# SensorBoard-v13.net
KiCad netlist of a schematic drawn in EAGLE
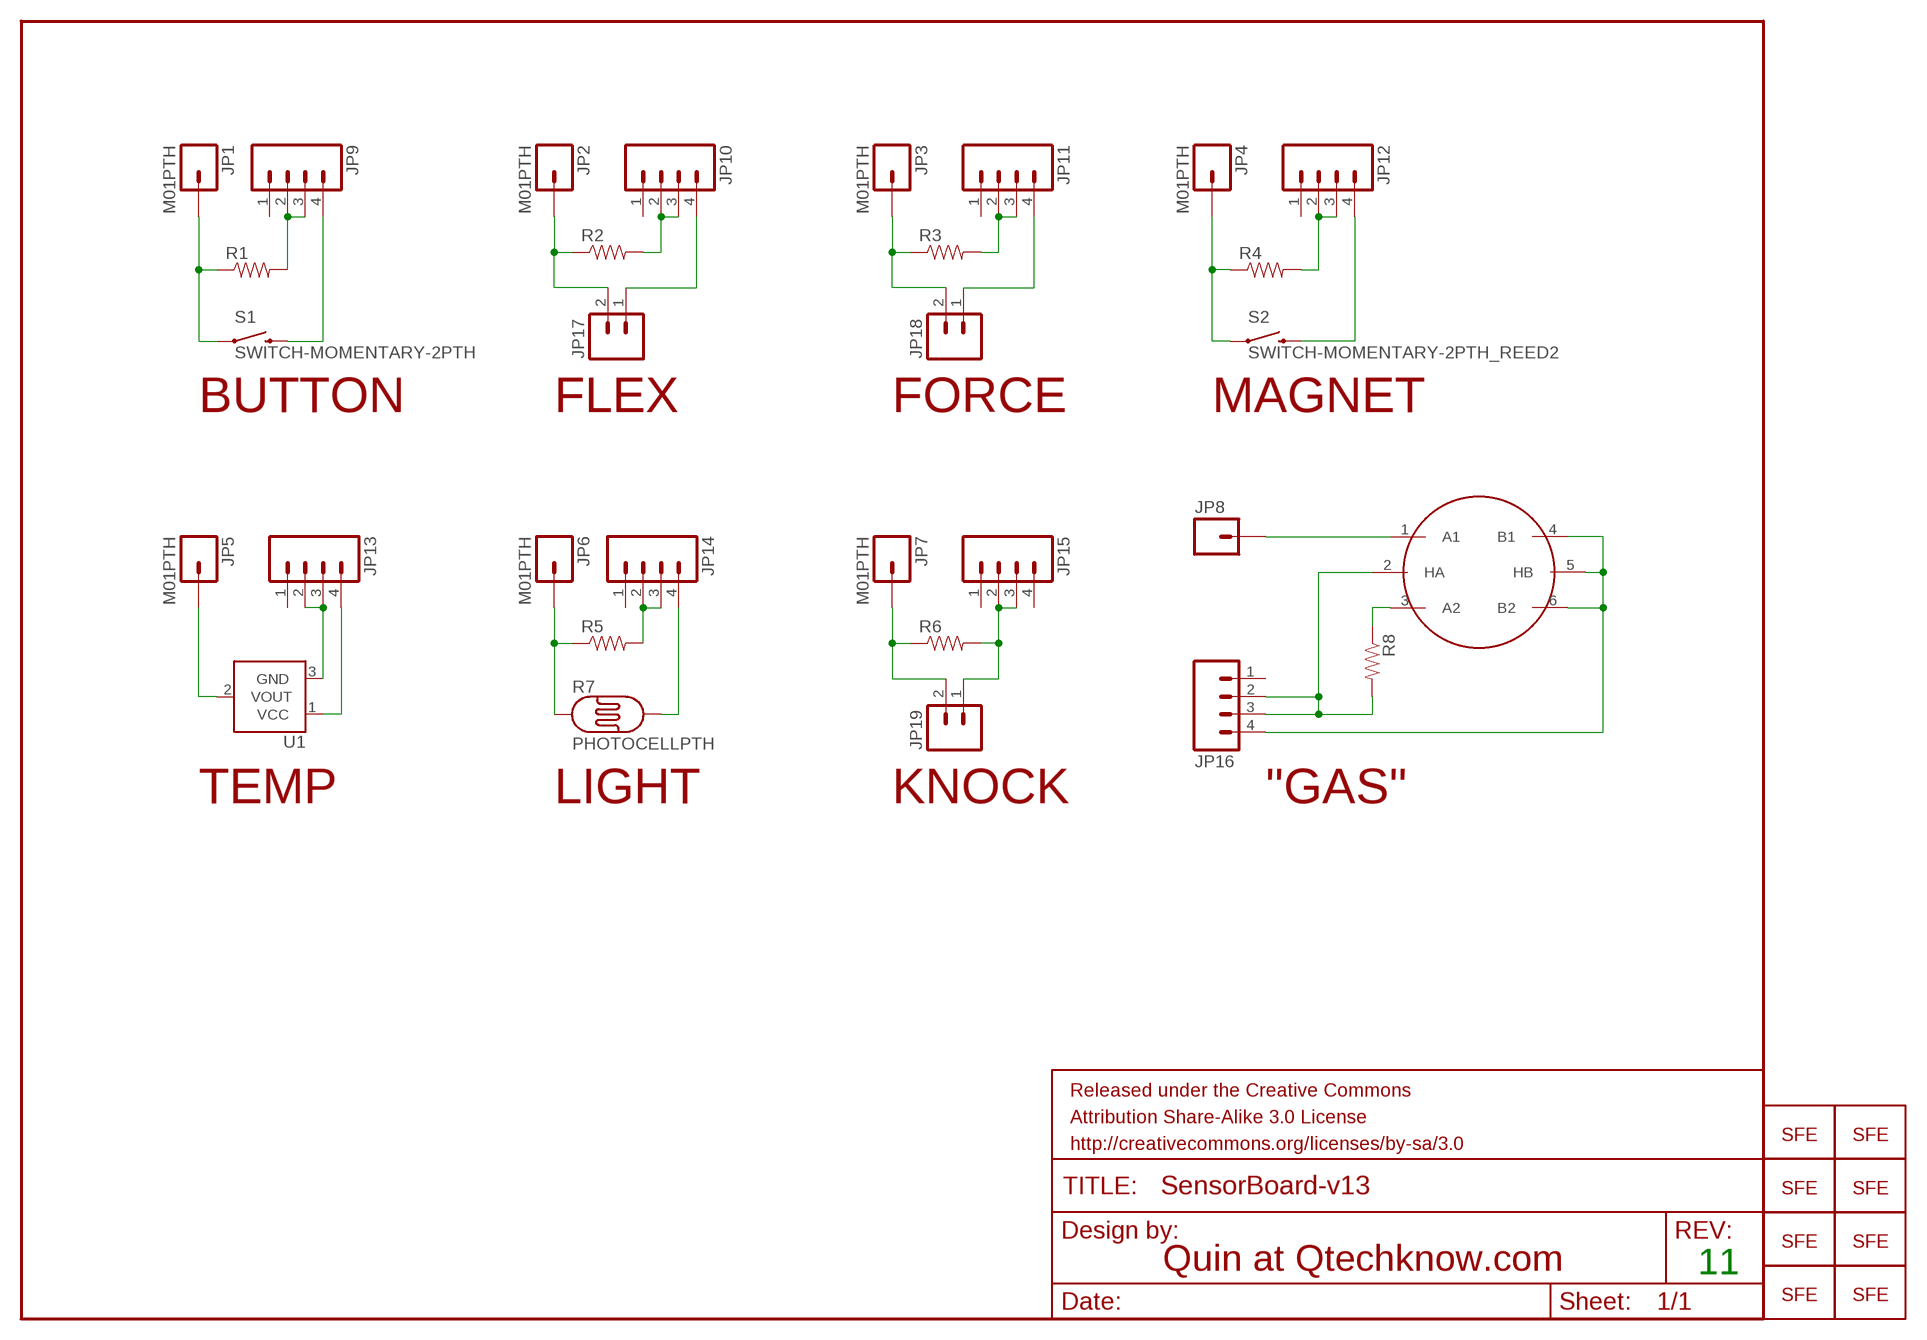
[diagram p0: schematic, sheet 1]

(export (version "E")
  (design (tool "Eeschema 10.0.6"))
  (components
    (comp (ref "FRAME1")
      (value "FRAME-LETTER")
      (footprint "eagle-import:CREATIVE_COMMONS")
      (libsource (lib "eagle-import") (part "FRAME-LETTER"))
    )
    (comp (ref "JP1")
      (value "M01PTH")
      (footprint "eagle-import:1X01")
      (libsource (lib "eagle-import") (part "2_1_SFE Connectors_M01PTH"))
    )
    (comp (ref "JP2")
      (value "M01PTH")
      (footprint "eagle-import:1X01")
      (libsource (lib "eagle-import") (part "2_2_SFE Connectors_M01PTH"))
    )
    (comp (ref "JP3")
      (value "M01PTH")
      (footprint "eagle-import:1X01")
      (libsource (lib "eagle-import") (part "2_3_SFE Connectors_M01PTH"))
    )
    (comp (ref "JP4")
      (value "M01PTH")
      (footprint "eagle-import:1X01")
      (libsource (lib "eagle-import") (part "2_6_SFE Connectors_M01PTH"))
    )
    (comp (ref "JP5")
      (value "M01PTH")
      (footprint "eagle-import:1X01")
      (libsource (lib "eagle-import") (part "2_7_SFE Connectors_M01PTH"))
    )
    (comp (ref "JP6")
      (value "M01PTH")
      (footprint "eagle-import:1X01")
      (libsource (lib "eagle-import") (part "2_5_SFE Connectors_M01PTH"))
    )
    (comp (ref "JP7")
      (value "M01PTH")
      (footprint "eagle-import:1X01")
      (libsource (lib "eagle-import") (part "2_4_SFE Connectors_M01PTH"))
    )
    (comp (ref "JP8")
      (value "M01PTH")
      (footprint "eagle-import:1X01")
      (libsource (lib "eagle-import") (part "M01PTH"))
    )
    (comp (ref "JP9")
      (value "M04PTH")
      (footprint "eagle-import:1X04")
      (libsource (lib "eagle-import") (part "2_1_SFE Connectors_M04PTH"))
    )
    (comp (ref "JP10")
      (value "M04PTH")
      (footprint "eagle-import:1X04")
      (libsource (lib "eagle-import") (part "2_2_SFE Connectors_M04PTH"))
    )
    (comp (ref "JP11")
      (value "M04PTH")
      (footprint "eagle-import:1X04")
      (libsource (lib "eagle-import") (part "2_3_SFE Connectors_M04PTH"))
    )
    (comp (ref "JP12")
      (value "M04PTH")
      (footprint "eagle-import:1X04")
      (libsource (lib "eagle-import") (part "2_6_SFE Connectors_M04PTH"))
    )
    (comp (ref "JP13")
      (value "M04PTH")
      (footprint "eagle-import:1X04")
      (libsource (lib "eagle-import") (part "2_7_SFE Connectors_M04PTH"))
    )
    (comp (ref "JP14")
      (value "M04PTH")
      (footprint "eagle-import:1X04")
      (libsource (lib "eagle-import") (part "2_5_SFE Connectors_M04PTH"))
    )
    (comp (ref "JP15")
      (value "M04PTH")
      (footprint "eagle-import:1X04")
      (libsource (lib "eagle-import") (part "2_4_SFE Connectors_M04PTH"))
    )
    (comp (ref "JP16")
      (value "M04PTH")
      (footprint "eagle-import:1X04")
      (libsource (lib "eagle-import") (part "M04PTH"))
    )
    (comp (ref "JP17")
      (value "M02PTH")
      (footprint "eagle-import:1X02")
      (libsource (lib "eagle-import") (part "M02PTH"))
    )
    (comp (ref "JP18")
      (value "M02PTH")
      (footprint "eagle-import:1X02")
      (libsource (lib "eagle-import") (part "2_3_SFE Connectors_M02PTH"))
    )
    (comp (ref "JP19")
      (value "M02PTH")
      (footprint "eagle-import:1X02")
      (libsource (lib "eagle-import") (part "2_4_SFE Connectors_M02PTH"))
    )
    (comp (ref "LOGO1")
      (value "LOGO-SFESK")
      (footprint "eagle-import:SFE-LOGO-FLAME")
      (libsource (lib "eagle-import") (part "LOGO-SFESK"))
    )
    (comp (ref "LOGO2")
      (value "LOGO-SFESK")
      (footprint "eagle-import:SFE-LOGO-FLAME")
      (libsource (lib "eagle-import") (part "LOGO-SFESK"))
    )
    (comp (ref "LOGO3")
      (value "LOGO-SFESK")
      (footprint "eagle-import:SFE-LOGO-FLAME")
      (libsource (lib "eagle-import") (part "LOGO-SFESK"))
    )
    (comp (ref "LOGO4")
      (value "LOGO-SFESK")
      (footprint "eagle-import:SFE-LOGO-FLAME")
      (libsource (lib "eagle-import") (part "LOGO-SFESK"))
    )
    (comp (ref "LOGO5")
      (value "LOGO-SFESK")
      (footprint "eagle-import:SFE-LOGO-FLAME")
      (libsource (lib "eagle-import") (part "LOGO-SFESK"))
    )
    (comp (ref "LOGO6")
      (value "LOGO-SFESK")
      (footprint "eagle-import:SFE-LOGO-FLAME")
      (libsource (lib "eagle-import") (part "LOGO-SFESK"))
    )
    (comp (ref "LOGO7")
      (value "LOGO-SFESK")
      (footprint "eagle-import:SFE-LOGO-FLAME")
      (libsource (lib "eagle-import") (part "LOGO-SFESK"))
    )
    (comp (ref "LOGO8")
      (value "LOGO-SFESK")
      (footprint "eagle-import:SFE-LOGO-FLAME")
      (libsource (lib "eagle-import") (part "LOGO-SFESK"))
    )
    (comp (ref "R1")
      (value "RESISTORAXIAL-0.3")
      (footprint "eagle-import:AXIAL-0.3")
      (libsource (lib "eagle-import") (part "2_1_SFE Passives_RESISTORAXIAL-0.3"))
    )
    (comp (ref "R2")
      (value "RESISTORAXIAL-0.3")
      (footprint "eagle-import:AXIAL-0.3")
      (libsource (lib "eagle-import") (part "2_2_SFE Passives_RESISTORAXIAL-0.3"))
    )
    (comp (ref "R3")
      (value "RESISTORAXIAL-0.3")
      (footprint "eagle-import:AXIAL-0.3")
      (libsource (lib "eagle-import") (part "2_3_SFE Passives_RESISTORAXIAL-0.3"))
    )
    (comp (ref "R4")
      (value "RESISTORAXIAL-0.3")
      (footprint "eagle-import:AXIAL-0.3")
      (libsource (lib "eagle-import") (part "2_6_SFE Passives_RESISTORAXIAL-0.3"))
    )
    (comp (ref "R5")
      (value "RESISTORAXIAL-0.3")
      (footprint "eagle-import:AXIAL-0.3")
      (libsource (lib "eagle-import") (part "2_5_SFE Passives_RESISTORAXIAL-0.3"))
    )
    (comp (ref "R6")
      (value "RESISTORAXIAL-0.3")
      (footprint "eagle-import:AXIAL-0.3")
      (libsource (lib "eagle-import") (part "2_4_SFE Passives_RESISTORAXIAL-0.3"))
    )
    (comp (ref "R7")
      (value "PHOTOCELLPTH")
      (footprint "eagle-import:PHOTOCELL")
      (libsource (lib "eagle-import") (part "PHOTOCELLPTH"))
    )
    (comp (ref "R8")
      (value "RESISTORAXIAL-0.3")
      (footprint "eagle-import:AXIAL-0.3")
      (libsource (lib "eagle-import") (part "RESISTORAXIAL-0.3"))
    )
    (comp (ref "S1")
      (value "SWITCH-MOMENTARY-2PTH")
      (footprint "eagle-import:TACTILE-PTH")
      (libsource (lib "eagle-import") (part "SWITCH-MOMENTARY-2PTH"))
    )
    (comp (ref "S2")
      (value "SWITCH-MOMENTARY-2PTH_REED2")
      (footprint "eagle-import:REED_SWITCH_PLASTIC")
      (libsource (lib "eagle-import") (part "2_6_SFE Electromechanical_SWITCH-MOMENTARY-2PTH_REED2"))
    )
    (comp (ref "U$1")
      (value "GAS-SENSORNEW")
      (footprint "eagle-import:GAS_SENSOR")
      (libsource (lib "eagle-import") (part "GAS-SENSORNEW"))
    )
    (comp (ref "U1")
      (value "TMP36GT9")
      (footprint "eagle-import:TO-92")
      (libsource (lib "eagle-import") (part "TMP36GT9"))
    )
  )
  (nets
    (net (code "1") (name "Net-(JP10-Pad4)") (class "Default")
      (node (ref "JP10") (pin "4") (pinfunction "4_4") (pintype "passive"))
      (node (ref "JP17") (pin "1") (pinfunction "1_1") (pintype "passive"))
    )
    (net (code "2") (name "Net-(JP11-Pad4)") (class "Default")
      (node (ref "JP11") (pin "4") (pinfunction "4_4") (pintype "passive"))
      (node (ref "JP18") (pin "1") (pinfunction "1_1") (pintype "passive"))
    )
    (net (code "3") (name "Net-(R1-1)") (class "Default")
      (node (ref "JP1") (pin "1") (pinfunction "1_1") (pintype "passive"))
      (node (ref "R1") (pin "P$1") (pinfunction "1_P$1") (pintype "passive"))
      (node (ref "S1") (pin "1") (pinfunction "1_1") (pintype "passive"))
    )
    (net (code "4") (name "Net-(R1-2)") (class "Default")
      (node (ref "JP9") (pin "2") (pinfunction "2_2") (pintype "passive"))
      (node (ref "JP9") (pin "3") (pinfunction "3_3") (pintype "passive"))
      (node (ref "R1") (pin "P$2") (pinfunction "2_P$2") (pintype "passive"))
    )
    (net (code "5") (name "Net-(R2-1)") (class "Default")
      (node (ref "JP17") (pin "2") (pinfunction "2_2") (pintype "passive"))
      (node (ref "JP2") (pin "1") (pinfunction "1_1") (pintype "passive"))
      (node (ref "R2") (pin "P$1") (pinfunction "1_P$1") (pintype "passive"))
    )
    (net (code "6") (name "Net-(R2-2)") (class "Default")
      (node (ref "JP10") (pin "2") (pinfunction "2_2") (pintype "passive"))
      (node (ref "JP10") (pin "3") (pinfunction "3_3") (pintype "passive"))
      (node (ref "R2") (pin "P$2") (pinfunction "2_P$2") (pintype "passive"))
    )
    (net (code "7") (name "Net-(R3-1)") (class "Default")
      (node (ref "JP18") (pin "2") (pinfunction "2_2") (pintype "passive"))
      (node (ref "JP3") (pin "1") (pinfunction "1_1") (pintype "passive"))
      (node (ref "R3") (pin "P$1") (pinfunction "1_P$1") (pintype "passive"))
    )
    (net (code "8") (name "Net-(R3-2)") (class "Default")
      (node (ref "JP11") (pin "2") (pinfunction "2_2") (pintype "passive"))
      (node (ref "JP11") (pin "3") (pinfunction "3_3") (pintype "passive"))
      (node (ref "R3") (pin "P$2") (pinfunction "2_P$2") (pintype "passive"))
    )
    (net (code "9") (name "Net-(R4-1)") (class "Default")
      (node (ref "JP4") (pin "1") (pinfunction "1_1") (pintype "passive"))
      (node (ref "R4") (pin "P$1") (pinfunction "1_P$1") (pintype "passive"))
      (node (ref "S2") (pin "P$1") (pinfunction "1_P$1") (pintype "passive"))
    )
    (net (code "10") (name "Net-(R4-2)") (class "Default")
      (node (ref "JP12") (pin "2") (pinfunction "2_2") (pintype "passive"))
      (node (ref "JP12") (pin "3") (pinfunction "3_3") (pintype "passive"))
      (node (ref "R4") (pin "P$2") (pinfunction "2_P$2") (pintype "passive"))
    )
    (net (code "11") (name "Net-(R5-1)") (class "Default")
      (node (ref "JP6") (pin "1") (pinfunction "1_1") (pintype "passive"))
      (node (ref "R5") (pin "P$1") (pinfunction "1_P$1") (pintype "passive"))
      (node (ref "R7") (pin "1") (pinfunction "P$1_1") (pintype "bidirectional"))
    )
    (net (code "12") (name "Net-(R5-2)") (class "Default")
      (node (ref "JP14") (pin "2") (pinfunction "2_2") (pintype "passive"))
      (node (ref "JP14") (pin "3") (pinfunction "3_3") (pintype "passive"))
      (node (ref "R5") (pin "P$2") (pinfunction "2_P$2") (pintype "passive"))
    )
    (net (code "13") (name "Net-(R6-1)") (class "Default")
      (node (ref "JP19") (pin "2") (pinfunction "2_2") (pintype "passive"))
      (node (ref "JP7") (pin "1") (pinfunction "1_1") (pintype "passive"))
      (node (ref "R6") (pin "P$1") (pinfunction "1_P$1") (pintype "passive"))
    )
    (net (code "14") (name "Net-(R6-2)") (class "Default")
      (node (ref "JP15") (pin "2") (pinfunction "2_2") (pintype "passive"))
      (node (ref "JP15") (pin "3") (pinfunction "3_3") (pintype "passive"))
      (node (ref "JP19") (pin "1") (pinfunction "1_1") (pintype "passive"))
      (node (ref "R6") (pin "P$2") (pinfunction "2_P$2") (pintype "passive"))
    )
    (net (code "15") (name "Net-(R7-P$2)") (class "Default")
      (node (ref "JP14") (pin "4") (pinfunction "4_4") (pintype "passive"))
      (node (ref "R7") (pin "2") (pinfunction "P$2_2") (pintype "bidirectional"))
    )
    (net (code "16") (name "Net-(R8-1)") (class "Default")
      (node (ref "R8") (pin "P$1") (pinfunction "1_P$1") (pintype "passive"))
      (node (ref "U$1") (pin "3") (pinfunction "A2_3") (pintype "bidirectional"))
    )
    (net (code "17") (name "Net-(R8-2)") (class "Default")
      (node (ref "JP16") (pin "2") (pinfunction "2_2") (pintype "passive"))
      (node (ref "JP16") (pin "3") (pinfunction "3_3") (pintype "passive"))
      (node (ref "R8") (pin "P$2") (pinfunction "2_P$2") (pintype "passive"))
      (node (ref "U$1") (pin "2") (pinfunction "HA_2") (pintype "bidirectional"))
    )
    (net (code "18") (name "Net-(S1-2)") (class "Default")
      (node (ref "JP9") (pin "4") (pinfunction "4_4") (pintype "passive"))
      (node (ref "S1") (pin "3") (pinfunction "2_3") (pintype "passive"))
    )
    (net (code "19") (name "Net-(S2-2)") (class "Default")
      (node (ref "JP12") (pin "4") (pinfunction "4_4") (pintype "passive"))
      (node (ref "S2") (pin "P$2") (pinfunction "2_P$2") (pintype "passive"))
    )
    (net (code "20") (name "Net-(U$1-A1)") (class "Default")
      (node (ref "JP8") (pin "1") (pinfunction "1_1") (pintype "passive"))
      (node (ref "U$1") (pin "1") (pinfunction "A1_1") (pintype "bidirectional"))
    )
    (net (code "21") (name "Net-(U$1-B1)") (class "Default")
      (node (ref "JP16") (pin "4") (pinfunction "4_4") (pintype "passive"))
      (node (ref "U$1") (pin "4") (pinfunction "B1_4") (pintype "bidirectional"))
      (node (ref "U$1") (pin "5") (pinfunction "HB_5") (pintype "bidirectional"))
      (node (ref "U$1") (pin "6") (pinfunction "B2_6") (pintype "bidirectional"))
    )
    (net (code "22") (name "Net-(U1-GND)") (class "Default")
      (node (ref "JP13") (pin "2") (pinfunction "2_2") (pintype "passive"))
      (node (ref "JP13") (pin "3") (pinfunction "3_3") (pintype "passive"))
      (node (ref "U1") (pin "3") (pinfunction "GND_3") (pintype "bidirectional"))
    )
    (net (code "23") (name "Net-(U1-VCC)") (class "Default")
      (node (ref "JP13") (pin "4") (pinfunction "4_4") (pintype "passive"))
      (node (ref "U1") (pin "1") (pinfunction "VCC_1") (pintype "bidirectional"))
    )
    (net (code "24") (name "Net-(U1-VOUT)") (class "Default")
      (node (ref "JP5") (pin "1") (pinfunction "1_1") (pintype "passive"))
      (node (ref "U1") (pin "2") (pinfunction "VOUT_2") (pintype "bidirectional"))
    )
    (net (code "25") (name "unconnected-(JP9-Pad1)") (class "Default")
      (node (ref "JP9") (pin "1") (pinfunction "1_1") (pintype "passive"))
    )
    (net (code "26") (name "unconnected-(JP10-Pad1)") (class "Default")
      (node (ref "JP10") (pin "1") (pinfunction "1_1") (pintype "passive"))
    )
    (net (code "27") (name "unconnected-(JP11-Pad1)") (class "Default")
      (node (ref "JP11") (pin "1") (pinfunction "1_1") (pintype "passive"))
    )
    (net (code "28") (name "unconnected-(JP12-Pad1)") (class "Default")
      (node (ref "JP12") (pin "1") (pinfunction "1_1") (pintype "passive"))
    )
    (net (code "29") (name "unconnected-(JP13-Pad1)") (class "Default")
      (node (ref "JP13") (pin "1") (pinfunction "1_1") (pintype "passive"))
    )
    (net (code "30") (name "unconnected-(JP14-Pad1)") (class "Default")
      (node (ref "JP14") (pin "1") (pinfunction "1_1") (pintype "passive"))
    )
    (net (code "31") (name "unconnected-(JP15-Pad1)") (class "Default")
      (node (ref "JP15") (pin "1") (pinfunction "1_1") (pintype "passive"))
    )
    (net (code "32") (name "unconnected-(JP15-Pad4)") (class "Default")
      (node (ref "JP15") (pin "4") (pinfunction "4_4") (pintype "passive"))
    )
    (net (code "33") (name "unconnected-(JP16-Pad1)") (class "Default")
      (node (ref "JP16") (pin "1") (pinfunction "1_1") (pintype "passive"))
    )
  )
)
